# 5V_Buck.net
KiCad netlist of a schematic drawn in Altium Designer
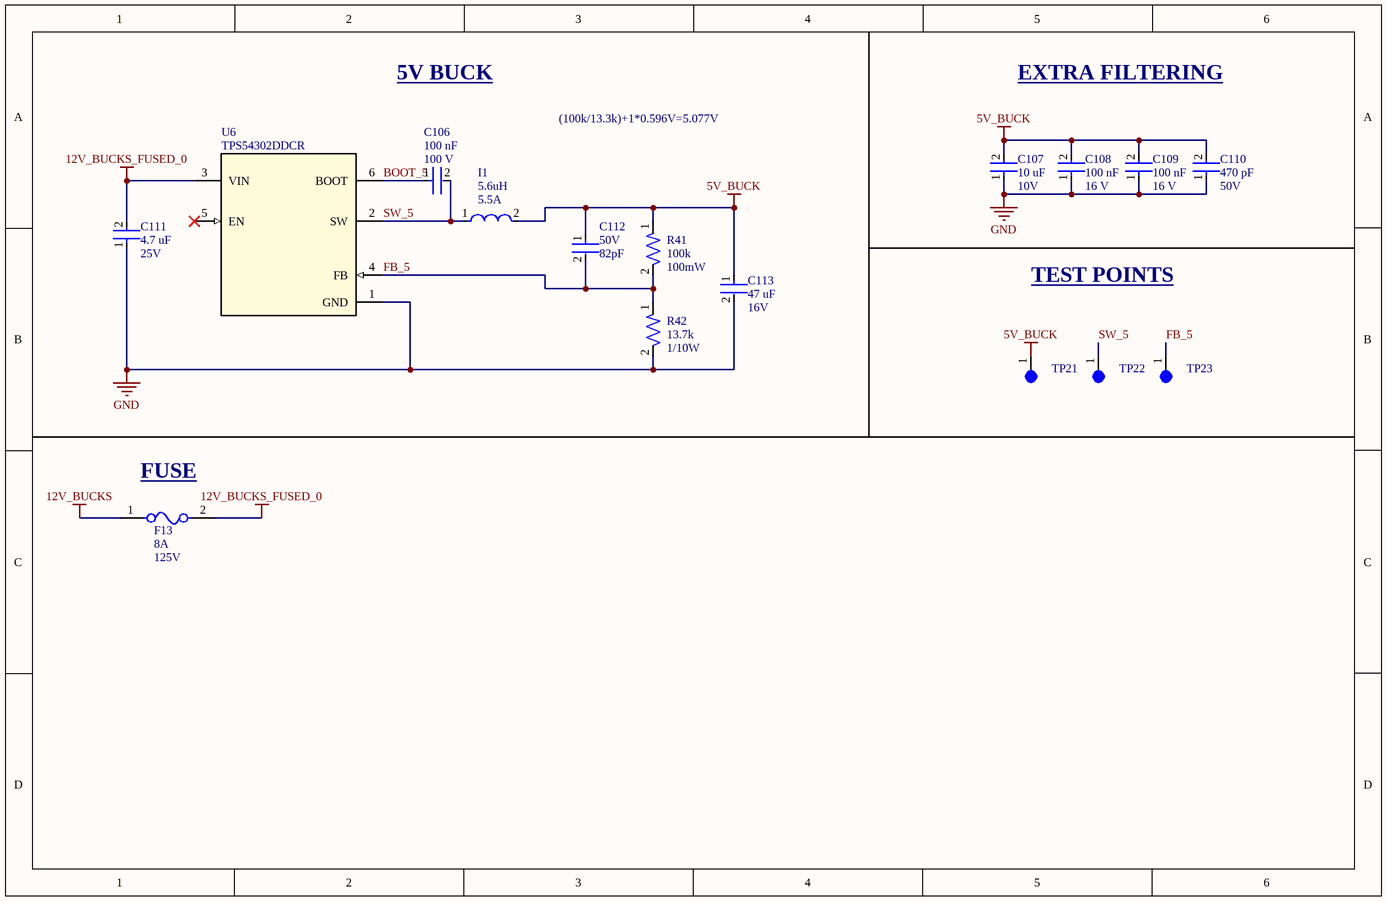
[diagram p0: 5V_Buck.SchDoc]

(export (version "E")
  (design (tool "Eeschema 10.0.6"))
  (components
    (comp (ref "C106")
      (value "CC0603KRX7R0BB104")
      (footprint "CAP-0603")
      (description "CAP CER 0.1UF 100V X7R 0603")
      (fields (field (name "CAPACITANCE") "100 nF") (field (name "VOLTAGE") "100 V"))
      (libsource (lib "JLC_25") (part "CAP-100N-0001"))
    )
    (comp (ref "C107")
      (value "CC0603KRX5R6BB106")
      (footprint "CAP-0603")
      (description "CAP CER 10UF 10V X5R 0603")
      (fields (field (name "VOLTAGE") "10V") (field (name "CAPACITANCE") "10 uF"))
      (libsource (lib "JLC_25") (part "CAP-10U-0001"))
    )
    (comp (ref "C108")
      (value "CC0402KRX7R7BB104")
      (footprint "CAP-0402")
      (description "CAP CER 0.1UF 16V X7R 0402")
      (fields (field (name "VOLTAGE RATING") "16 V") (field (name "CAPACITANCE") "100 nF"))
      (libsource (lib "JLC_25") (part "CAP-0.1U-0001"))
    )
    (comp (ref "C109")
      (value "CC0402KRX7R7BB104")
      (footprint "CAP-0402")
      (description "CAP CER 0.1UF 16V X7R 0402")
      (fields (field (name "VOLTAGE RATING") "16 V") (field (name "CAPACITANCE") "100 nF"))
      (libsource (lib "JLC_25") (part "CAP-0.1U-0001"))
    )
    (comp (ref "C110")
      (value "CC0805JRNPO9BN471")
      (footprint "CAP-0805")
      (description "CAP CER 470PF 50V C0G/NPO 0805")
      (fields (field (name "VOLTAGE") "50V") (field (name "CAPACITANCE") "470 pF"))
      (libsource (lib "JLC_25") (part "CAP-470P-0001"))
    )
    (comp (ref "C111")
      (value "CC0603KRX5R8BB475")
      (footprint "CAP-0603")
      (description "CAP CER 4.7UF 25V X5R 0603")
      (fields (field (name "CAPACITANCE") "4.7 uF") (field (name "VOLTAGE") "25V"))
      (libsource (lib "JLC_25") (part "CAP-4.7U-0001"))
    )
    (comp (ref "C112")
      (value "CC0805JRNPO9BN820")
      (footprint "CAP-0805")
      (description "82 pF ±5% 50V Ceramic Capacitor C0G, NP0 0805 (2012 Metric)")
      (fields (field (name "VOLTAGE") "50V") (field (name "CAPACITANCE") "82pF"))
      (libsource (lib "JLC_25") (part "CAP-82P-0001"))
    )
    (comp (ref "C113")
      (value "GRM32ER61C476KE15L")
      (footprint "CAP-1210")
      (description "CAP CER 47UF 16V X5R 1210")
      (fields (field (name "CAPACITANCE") "47 uF") (field (name "VOLTAGE") "16V"))
      (libsource (lib "JLC_25") (part "CAP-47U-0002"))
    )
    (comp (ref "F13")
      (value "01550900M")
      (footprint "FUSE-0001")
      (description "FUSE BLOK CARTRIDGE 125V 10A SMD")
      (fields (field (name "FUSE CURRENT") "8A") (field (name "VOLTAGE RATING") "125V"))
      (libsource (lib "JLC_25") (part "FUSE-0001"))
    )
    (comp (ref "I1")
      (value "SRP6540-5R6M")
      (footprint "IND_SRP6540-5R6M")
      (description "FIXED IND 5.6UH 5.5A 38 MOHM SMD")
      (fields (field (name "SATURATION CURRENT") "5.5A") (field (name "INDUCTANCE") "5.6uH"))
      (libsource (lib "JLC_25") (part "IND-5.6U-0002"))
    )
    (comp (ref "R41")
      (value "RC0603FR-07100KL")
      (footprint "RES-0603")
      (description "RES SMD 100K OHM 1% 1/10W 0603")
      (fields
        (field (name "TOLERANCE") "1%")
        (field (name "POWER") "100mW")
        (field (name "RESISTANCE") "100k")
      )
      (libsource (lib "JLC_25") (part "RES-100k-0001"))
    )
    (comp (ref "R42")
      (value "RC0603FR-0713K7L")
      (footprint "RES-0603")
      (description "RES 13.7K OHM 1% 1/10W 0603")
      (fields (field (name "POWER") "1/10W") (field (name "RESISTANCE") "13.7k"))
      (libsource (lib "JLC_25") (part "RES-13.7K-0001"))
    )
    (comp (ref "TP21")
      (value "5003")
      (footprint "TEST-POINT-0001")
      (description "Oranange PC Test Point, Miniature Phoisphor Bronze Silver Plating Through Hole Mounting Type")
      (libsource (lib "*") (part "TEST-POINT-0001"))
    )
    (comp (ref "TP22")
      (value "5003")
      (footprint "TEST-POINT-0001")
      (description "Oranange PC Test Point, Miniature Phoisphor Bronze Silver Plating Through Hole Mounting Type")
      (libsource (lib "*") (part "TEST-POINT-0001"))
    )
    (comp (ref "TP23")
      (value "5003")
      (footprint "TEST-POINT-0001")
      (description "Oranange PC Test Point, Miniature Phoisphor Bronze Silver Plating Through Hole Mounting Type")
      (libsource (lib "*") (part "TEST-POINT-0001"))
    )
    (comp (ref "U6")
      (value "TPS54302DDCR")
      (footprint "IC-SOT-23-6")
      (description "IC REG BUCK ADJ 3A SOT23")
      (libsource (lib "JLC_25") (part "IC-BUCK-0004"))
    )
  )
  (nets
    (net (code "1") (name "/BOOT_5") (class "Default")
      (node (ref "C106") (pin "1") (pinfunction "1_1") (pintype "passive"))
      (node (ref "U6") (pin "6") (pinfunction "BOOT_6") (pintype "power_in"))
    )
    (net (code "2") (name "/FB_5") (class "Default")
      (node (ref "C112") (pin "2") (pinfunction "2_2") (pintype "passive"))
      (node (ref "R41") (pin "2") (pinfunction "2_2") (pintype "passive"))
      (node (ref "R42") (pin "1") (pinfunction "1_1") (pintype "passive"))
      (node (ref "TP23") (pin "1") (pinfunction "0_1") (pintype "passive"))
      (node (ref "U6") (pin "4") (pinfunction "FB_4") (pintype "input"))
    )
    (net (code "3") (name "/SW_5") (class "Default")
      (node (ref "C106") (pin "2") (pinfunction "2_2") (pintype "passive"))
      (node (ref "I1") (pin "1") (pinfunction "1_1") (pintype "passive"))
      (node (ref "TP22") (pin "1") (pinfunction "0_1") (pintype "passive"))
      (node (ref "U6") (pin "2") (pinfunction "SW_2") (pintype "power_in"))
    )
    (net (code "4") (name "5V_BUCK") (class "Default")
      (node (ref "C107") (pin "2") (pinfunction "2_2") (pintype "passive"))
      (node (ref "C108") (pin "2") (pinfunction "2_2") (pintype "passive"))
      (node (ref "C109") (pin "2") (pinfunction "2_2") (pintype "passive"))
      (node (ref "C110") (pin "2") (pinfunction "2_2") (pintype "passive"))
      (node (ref "C112") (pin "1") (pinfunction "1_1") (pintype "passive"))
      (node (ref "C113") (pin "1") (pinfunction "1_1") (pintype "passive"))
      (node (ref "I1") (pin "2") (pinfunction "2_2") (pintype "passive"))
      (node (ref "R41") (pin "1") (pinfunction "1_1") (pintype "passive"))
      (node (ref "TP21") (pin "1") (pinfunction "0_1") (pintype "passive"))
    )
    (net (code "5") (name "12V_BUCKS") (class "Default")
      (node (ref "F13") (pin "1") (pinfunction "1_1") (pintype "passive"))
    )
    (net (code "6") (name "12V_BUCKS_FUSED_0") (class "Default")
      (node (ref "C111") (pin "2") (pinfunction "2_2") (pintype "passive"))
      (node (ref "F13") (pin "2") (pinfunction "2_2") (pintype "passive"))
      (node (ref "U6") (pin "3") (pinfunction "VIN_3") (pintype "power_in"))
    )
    (net (code "7") (name "GND") (class "Default")
      (node (ref "C107") (pin "1") (pinfunction "1_1") (pintype "passive"))
      (node (ref "C108") (pin "1") (pinfunction "1_1") (pintype "passive"))
      (node (ref "C109") (pin "1") (pinfunction "1_1") (pintype "passive"))
      (node (ref "C110") (pin "1") (pinfunction "1_1") (pintype "passive"))
      (node (ref "C111") (pin "1") (pinfunction "1_1") (pintype "passive"))
      (node (ref "C113") (pin "2") (pinfunction "2_2") (pintype "passive"))
      (node (ref "R42") (pin "2") (pinfunction "2_2") (pintype "passive"))
      (node (ref "U6") (pin "1") (pinfunction "GND_1") (pintype "power_in"))
    )
    (net (code "8") (name "unconnected-(U6-EN-Pad5)") (class "Default")
      (node (ref "U6") (pin "5") (pinfunction "EN_5") (pintype "input+no_connect"))
    )
  )
)
